# Infrarrojo.net
KiCad netlist of a schematic drawn in EAGLE
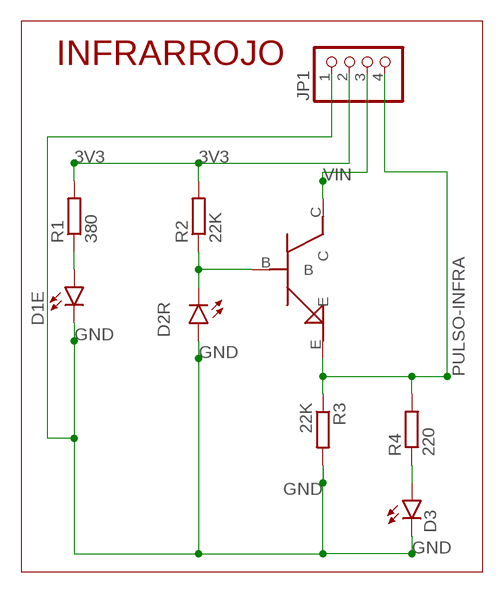
[diagram p0: schematic, sheet 1]

(export (version "E")
  (design (tool "Eeschema 10.0.6"))
  (components
    (comp (ref "D1E")
      (value "LED3MM")
      (footprint "eagle-import:LED3MM")
      (libsource (lib "eagle-import") (part "LED3MM"))
    )
    (comp (ref "D2R")
      (value "LED3MM")
      (footprint "eagle-import:LED3MM")
      (libsource (lib "eagle-import") (part "LED3MM"))
    )
    (comp (ref "D3")
      (value "LED3MM")
      (footprint "eagle-import:LED3MM")
      (libsource (lib "eagle-import") (part "LED3MM"))
    )
    (comp (ref "JP1")
      (value "PINHD-1X4")
      (footprint "eagle-import:1X04")
      (libsource (lib "eagle-import") (part "PINHD-1X4"))
    )
    (comp (ref "R1")
      (value "380")
      (footprint "eagle-import:0204_7")
      (libsource (lib "eagle-import") (part "R-EU_0204/7"))
    )
    (comp (ref "R2")
      (value "22K")
      (footprint "eagle-import:0204_7")
      (libsource (lib "eagle-import") (part "R-EU_0204/7"))
    )
    (comp (ref "R3")
      (value "22K")
      (footprint "eagle-import:0204_7")
      (libsource (lib "eagle-import") (part "R-EU_0204/7"))
    )
    (comp (ref "R4")
      (value "220")
      (footprint "eagle-import:0204_7")
      (libsource (lib "eagle-import") (part "R-EU_0204/7"))
    )
    (comp (ref "U$1")
      (value "2N2222")
      (footprint "eagle-import:2N2222")
      (libsource (lib "eagle-import") (part "2N2222"))
    )
  )
  (nets
    (net (code "1") (name "/3V3") (class "Default")
      (node (ref "JP1") (pin "2") (pinfunction "2_2") (pintype "passive"))
      (node (ref "R1") (pin "2") (pinfunction "2_2") (pintype "passive"))
      (node (ref "R2") (pin "2") (pinfunction "2_2") (pintype "passive"))
    )
    (net (code "2") (name "/GND") (class "Default")
      (node (ref "D1E") (pin "K") (pinfunction "C_K") (pintype "passive"))
      (node (ref "D2R") (pin "A") (pinfunction "A_A") (pintype "passive"))
      (node (ref "D3") (pin "K") (pinfunction "C_K") (pintype "passive"))
      (node (ref "JP1") (pin "1") (pinfunction "1_1") (pintype "passive"))
      (node (ref "R3") (pin "2") (pinfunction "2_2") (pintype "passive"))
    )
    (net (code "3") (name "/PULSO-INFRA") (class "Default")
      (node (ref "JP1") (pin "4") (pinfunction "4_4") (pintype "passive"))
      (node (ref "R3") (pin "1") (pinfunction "1_1") (pintype "passive"))
      (node (ref "R4") (pin "2") (pinfunction "2_2") (pintype "passive"))
      (node (ref "U$1") (pin "E") (pinfunction "E_E") (pintype "bidirectional"))
    )
    (net (code "4") (name "/VIN") (class "Default")
      (node (ref "JP1") (pin "3") (pinfunction "3_3") (pintype "passive"))
      (node (ref "U$1") (pin "C") (pinfunction "C_C") (pintype "bidirectional"))
    )
    (net (code "5") (name "Net-(D1E-PadA)") (class "Default")
      (node (ref "D1E") (pin "A") (pinfunction "A_A") (pintype "passive"))
      (node (ref "R1") (pin "1") (pinfunction "1_1") (pintype "passive"))
    )
    (net (code "6") (name "Net-(D2R-C)") (class "Default")
      (node (ref "D2R") (pin "K") (pinfunction "C_K") (pintype "passive"))
      (node (ref "R2") (pin "1") (pinfunction "1_1") (pintype "passive"))
      (node (ref "U$1") (pin "B") (pinfunction "B_B") (pintype "bidirectional"))
    )
    (net (code "7") (name "Net-(D3-PadA)") (class "Default")
      (node (ref "D3") (pin "A") (pinfunction "A_A") (pintype "passive"))
      (node (ref "R4") (pin "1") (pinfunction "1_1") (pintype "passive"))
    )
  )
)
